# Grove_-_Barometer_Sensor_V0_9b.net
KiCad netlist of a schematic drawn in EAGLE
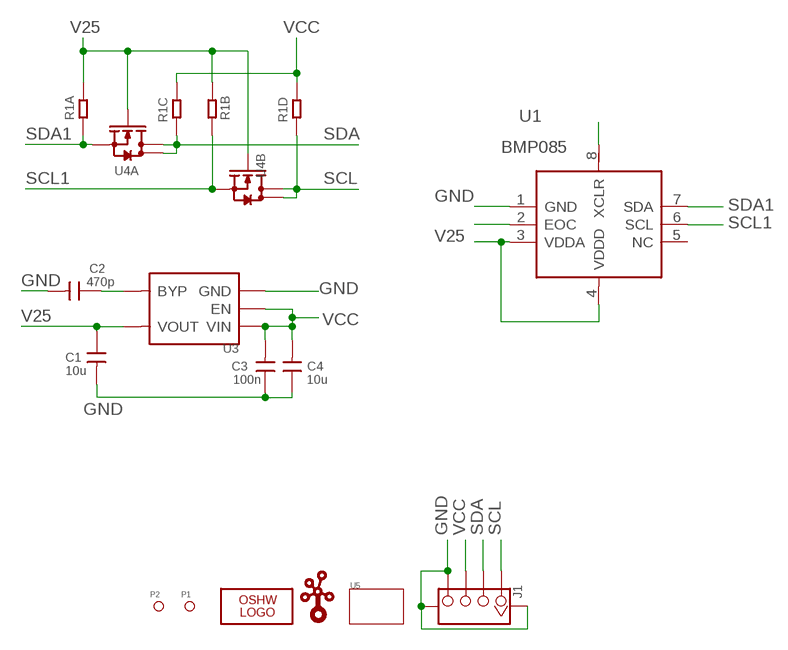
[diagram p0: schematic, sheet 1]

(export (version "E")
  (design (tool "Eeschema 10.0.6"))
  (components
    (comp (ref "C1")
      (value "10u")
      (footprint "eagle-import:0603")
      (libsource (lib "eagle-import") (part "C-0603"))
    )
    (comp (ref "C2")
      (value "470p")
      (footprint "eagle-import:0603")
      (libsource (lib "eagle-import") (part "C-0603"))
    )
    (comp (ref "C3")
      (value "100n")
      (footprint "eagle-import:0603")
      (libsource (lib "eagle-import") (part "C-0603"))
    )
    (comp (ref "C4")
      (value "10u")
      (footprint "eagle-import:0603")
      (libsource (lib "eagle-import") (part "C-0603"))
    )
    (comp (ref "J1")
      (value "TWIG-4P-2.0-SMD-FEMALE-REINFORCE'DD'")
      (footprint "eagle-import:4P-SMD-2.0")
      (libsource (lib "eagle-import") (part "TWIG-4P-2.0-SMD-FEMALE-REINFORCE'DD'"))
    )
    (comp (ref "LOGO2")
      (value "LOGO-OSHW-FILLX0200-NT")
      (footprint "eagle-import:OSHW_FILLX200_NOTEXT")
      (libsource (lib "eagle-import") (part "LOGO-OSHW-FILLX0200-NT"))
    )
    (comp (ref "P1")
      (value "PAD-MARK")
      (footprint "eagle-import:ROUND-MARK-0.635")
      (libsource (lib "eagle-import") (part "PAD-MARK"))
    )
    (comp (ref "P2")
      (value "PAD-MARK")
      (footprint "eagle-import:ROUND-MARK-0.635")
      (libsource (lib "eagle-import") (part "PAD-MARK"))
    )
    (comp (ref "R1")
      (value "R-4R-1206")
      (footprint "eagle-import:1206-8-3.3X2.4")
      (libsource (lib "eagle-import") (part "R-4R-1206"))
    )
    (comp (ref "U$1")
      (value "LOGO-TWIGTWIGLOGO_SMALL")
      (footprint "eagle-import:TWIGLOGO_SMALL")
      (libsource (lib "eagle-import") (part "LOGO-TWIGTWIGLOGO_SMALL"))
    )
    (comp (ref "U1")
      (value "BMP085")
      (footprint "eagle-import:LCC8")
      (libsource (lib "eagle-import") (part "BMP085"))
    )
    (comp (ref "U3")
      (value "MIC5205")
      (footprint "eagle-import:SOT23-5")
      (libsource (lib "eagle-import") (part "MIC5205"))
    )
    (comp (ref "U4")
      (value "MOSFET-DUAL-N-1206-8")
      (footprint "eagle-import:1206-8")
      (libsource (lib "eagle-import") (part "MOSFET-DUAL-N-1206-8"))
    )
    (comp (ref "U5")
      (value "TWIG-1U")
      (footprint "eagle-import:1U-DIM-W_-DRILL")
      (libsource (lib "eagle-import") (part "TWIG-1U"))
    )
  )
  (nets
    (net (code "1") (name "/GND") (class "Default")
      (node (ref "C1") (pin "2") (pinfunction "2_2") (pintype "passive"))
      (node (ref "C2") (pin "2") (pinfunction "2_2") (pintype "passive"))
      (node (ref "C3") (pin "1") (pinfunction "1_1") (pintype "passive"))
      (node (ref "C4") (pin "1") (pinfunction "1_1") (pintype "passive"))
      (node (ref "J1") (pin "4") (pinfunction "4_4") (pintype "bidirectional"))
      (node (ref "J1") (pin "SS1") (pinfunction "SS1_SS1") (pintype "bidirectional"))
      (node (ref "J1") (pin "SS2") (pinfunction "SS2_SS2") (pintype "bidirectional"))
      (node (ref "U1") (pin "1") (pinfunction "GND_1") (pintype "power_in"))
      (node (ref "U3") (pin "2") (pinfunction "GND_2") (pintype "bidirectional"))
    )
    (net (code "2") (name "/SCL") (class "Default")
      (node (ref "J1") (pin "1") (pinfunction "1_1") (pintype "bidirectional"))
      (node (ref "R1") (pin "4") (pinfunction "1_4") (pintype "passive"))
      (node (ref "U4") (pin "5") (pinfunction "D_5") (pintype "passive"))
      (node (ref "U4") (pin "6") (pinfunction "D_6") (pintype "passive"))
    )
    (net (code "3") (name "/SCL1") (class "Default")
      (node (ref "R1") (pin "7") (pinfunction "2_7") (pintype "passive"))
      (node (ref "U1") (pin "6") (pinfunction "SCL_6") (pintype "input"))
      (node (ref "U4") (pin "3") (pinfunction "S_3") (pintype "passive"))
    )
    (net (code "4") (name "/SDA") (class "Default")
      (node (ref "J1") (pin "2") (pinfunction "2_2") (pintype "bidirectional"))
      (node (ref "R1") (pin "3") (pinfunction "1_3") (pintype "passive"))
      (node (ref "U4") (pin "7") (pinfunction "D_7") (pintype "passive"))
      (node (ref "U4") (pin "8") (pinfunction "D_8") (pintype "passive"))
    )
    (net (code "5") (name "/SDA1") (class "Default")
      (node (ref "R1") (pin "1") (pinfunction "1_1") (pintype "passive"))
      (node (ref "U1") (pin "7") (pinfunction "SDA_7") (pintype "bidirectional"))
      (node (ref "U4") (pin "1") (pinfunction "S_1") (pintype "passive"))
    )
    (net (code "6") (name "/V25") (class "Default")
      (node (ref "C1") (pin "1") (pinfunction "1_1") (pintype "passive"))
      (node (ref "R1") (pin "2") (pinfunction "1_2") (pintype "passive"))
      (node (ref "R1") (pin "8") (pinfunction "2_8") (pintype "passive"))
      (node (ref "U1") (pin "3") (pinfunction "VDDA_3") (pintype "power_in"))
      (node (ref "U1") (pin "4") (pinfunction "VDDD_4") (pintype "power_in"))
      (node (ref "U3") (pin "5") (pinfunction "VOUT_5") (pintype "bidirectional"))
      (node (ref "U4") (pin "2") (pinfunction "G_2") (pintype "passive"))
      (node (ref "U4") (pin "4") (pinfunction "G_4") (pintype "passive"))
    )
    (net (code "7") (name "/VCC") (class "Default")
      (node (ref "C3") (pin "2") (pinfunction "2_2") (pintype "passive"))
      (node (ref "C4") (pin "2") (pinfunction "2_2") (pintype "passive"))
      (node (ref "J1") (pin "3") (pinfunction "3_3") (pintype "bidirectional"))
      (node (ref "R1") (pin "5") (pinfunction "2_5") (pintype "passive"))
      (node (ref "R1") (pin "6") (pinfunction "2_6") (pintype "passive"))
      (node (ref "U3") (pin "1") (pinfunction "VIN_1") (pintype "bidirectional"))
      (node (ref "U3") (pin "3") (pinfunction "EN_3") (pintype "bidirectional"))
    )
    (net (code "8") (name "Net-(U3-BYP)") (class "Default")
      (node (ref "C2") (pin "1") (pinfunction "1_1") (pintype "passive"))
      (node (ref "U3") (pin "4") (pinfunction "BYP_4") (pintype "bidirectional"))
    )
    (net (code "9") (name "unconnected-(U1-EOC-Pad2)") (class "Default")
      (node (ref "U1") (pin "2") (pinfunction "EOC_2") (pintype "output"))
    )
    (net (code "10") (name "unconnected-(U1-NC-Pad5)") (class "Default")
      (node (ref "U1") (pin "5") (pinfunction "NC_5") (pintype "no_connect"))
    )
    (net (code "11") (name "unconnected-(U1-XCLR-Pad8)") (class "Default")
      (node (ref "U1") (pin "8") (pinfunction "XCLR_8") (pintype "input"))
    )
  )
)
